# TinyBlinkRGB.net
KiCad netlist of a schematic drawn in EAGLE
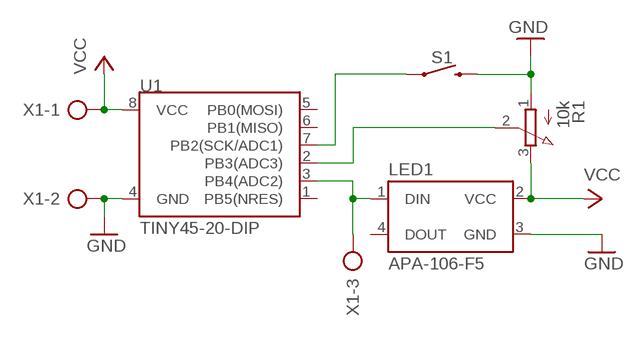
[diagram p0: schematic, sheet 1]

(export (version "E")
  (design (tool "Eeschema 10.0.6"))
  (components
    (comp (ref "LED1")
      (value "APA-106-F5")
      (footprint "eagle-import:APA-106-F5")
      (libsource (lib "eagle-import") (part "APA-106-F5"))
    )
    (comp (ref "R1")
      (value "10k")
      (footprint "eagle-import:3RP_1610N")
      (libsource (lib "eagle-import") (part "3RP/1610N"))
    )
    (comp (ref "S1")
      (value "MOMENTARY-SWITCH-SPST-PTH-6.0MM")
      (footprint "eagle-import:TACTILE_SWITCH_PTH_6.0MM")
      (libsource (lib "eagle-import") (part "MOMENTARY-SWITCH-SPST-PTH-6.0MM"))
    )
    (comp (ref "U1")
      (value "TINY45-20-DIP")
      (footprint "eagle-import:DIP08_MCU")
      (libsource (lib "eagle-import") (part "ATTINY45TINY45-20-DIP"))
    )
    (comp (ref "X1")
      (value "AK500/3")
      (footprint "eagle-import:AK500_3")
      (libsource (lib "eagle-import") (part "AK500/3"))
    )
  )
  (nets
    (net (code "1") (name "GND") (class "Default")
      (node (ref "LED1") (pin "3") (pinfunction "GND_3") (pintype "bidirectional"))
      (node (ref "R1") (pin "1") (pinfunction "A_1") (pintype "passive"))
      (node (ref "S1") (pin "3") (pinfunction "2_3") (pintype "passive"))
      (node (ref "U1") (pin "4") (pinfunction "GND_4") (pintype "bidirectional"))
      (node (ref "X1") (pin "2") (pinfunction "KL_2") (pintype "passive"))
    )
    (net (code "2") (name "Net-(LED1-DIN)") (class "Default")
      (node (ref "LED1") (pin "1") (pinfunction "DIN_1") (pintype "bidirectional"))
      (node (ref "U1") (pin "3") (pinfunction "PB4(ADC2)_3") (pintype "bidirectional"))
      (node (ref "X1") (pin "3") (pinfunction "KL_3") (pintype "passive"))
    )
    (net (code "3") (name "Net-(R1-S)") (class "Default")
      (node (ref "R1") (pin "2") (pinfunction "S_2") (pintype "passive"))
      (node (ref "U1") (pin "2") (pinfunction "PB3(ADC3)_2") (pintype "bidirectional"))
    )
    (net (code "4") (name "Net-(U1-PB2(SCK{slash}ADC1))") (class "Default")
      (node (ref "S1") (pin "1") (pinfunction "1_1") (pintype "passive"))
      (node (ref "U1") (pin "7") (pinfunction "PB2(SCK/ADC1)_7") (pintype "bidirectional"))
    )
    (net (code "5") (name "VCC") (class "Default")
      (node (ref "LED1") (pin "2") (pinfunction "VCC_2") (pintype "bidirectional"))
      (node (ref "R1") (pin "3") (pinfunction "E_3") (pintype "passive"))
      (node (ref "U1") (pin "8") (pinfunction "VCC_8") (pintype "bidirectional"))
      (node (ref "X1") (pin "1") (pinfunction "KL_1") (pintype "passive"))
    )
    (net (code "6") (name "unconnected-(LED1-DOUT-Pad4)") (class "Default")
      (node (ref "LED1") (pin "4") (pinfunction "DOUT_4") (pintype "bidirectional"))
    )
    (net (code "7") (name "unconnected-(U1-PB0(MOSI)-Pad5)") (class "Default")
      (node (ref "U1") (pin "5") (pinfunction "PB0(MOSI)_5") (pintype "bidirectional"))
    )
    (net (code "8") (name "unconnected-(U1-PB1(MISO)-Pad6)") (class "Default")
      (node (ref "U1") (pin "6") (pinfunction "PB1(MISO)_6") (pintype "bidirectional"))
    )
    (net (code "9") (name "unconnected-(U1-PB5(NRES)-Pad1)") (class "Default")
      (node (ref "U1") (pin "1") (pinfunction "PB5(NRES)_1") (pintype "bidirectional"))
    )
  )
)
